# EXT_TWI_LVC.net
KiCad netlist of a schematic drawn in EAGLE
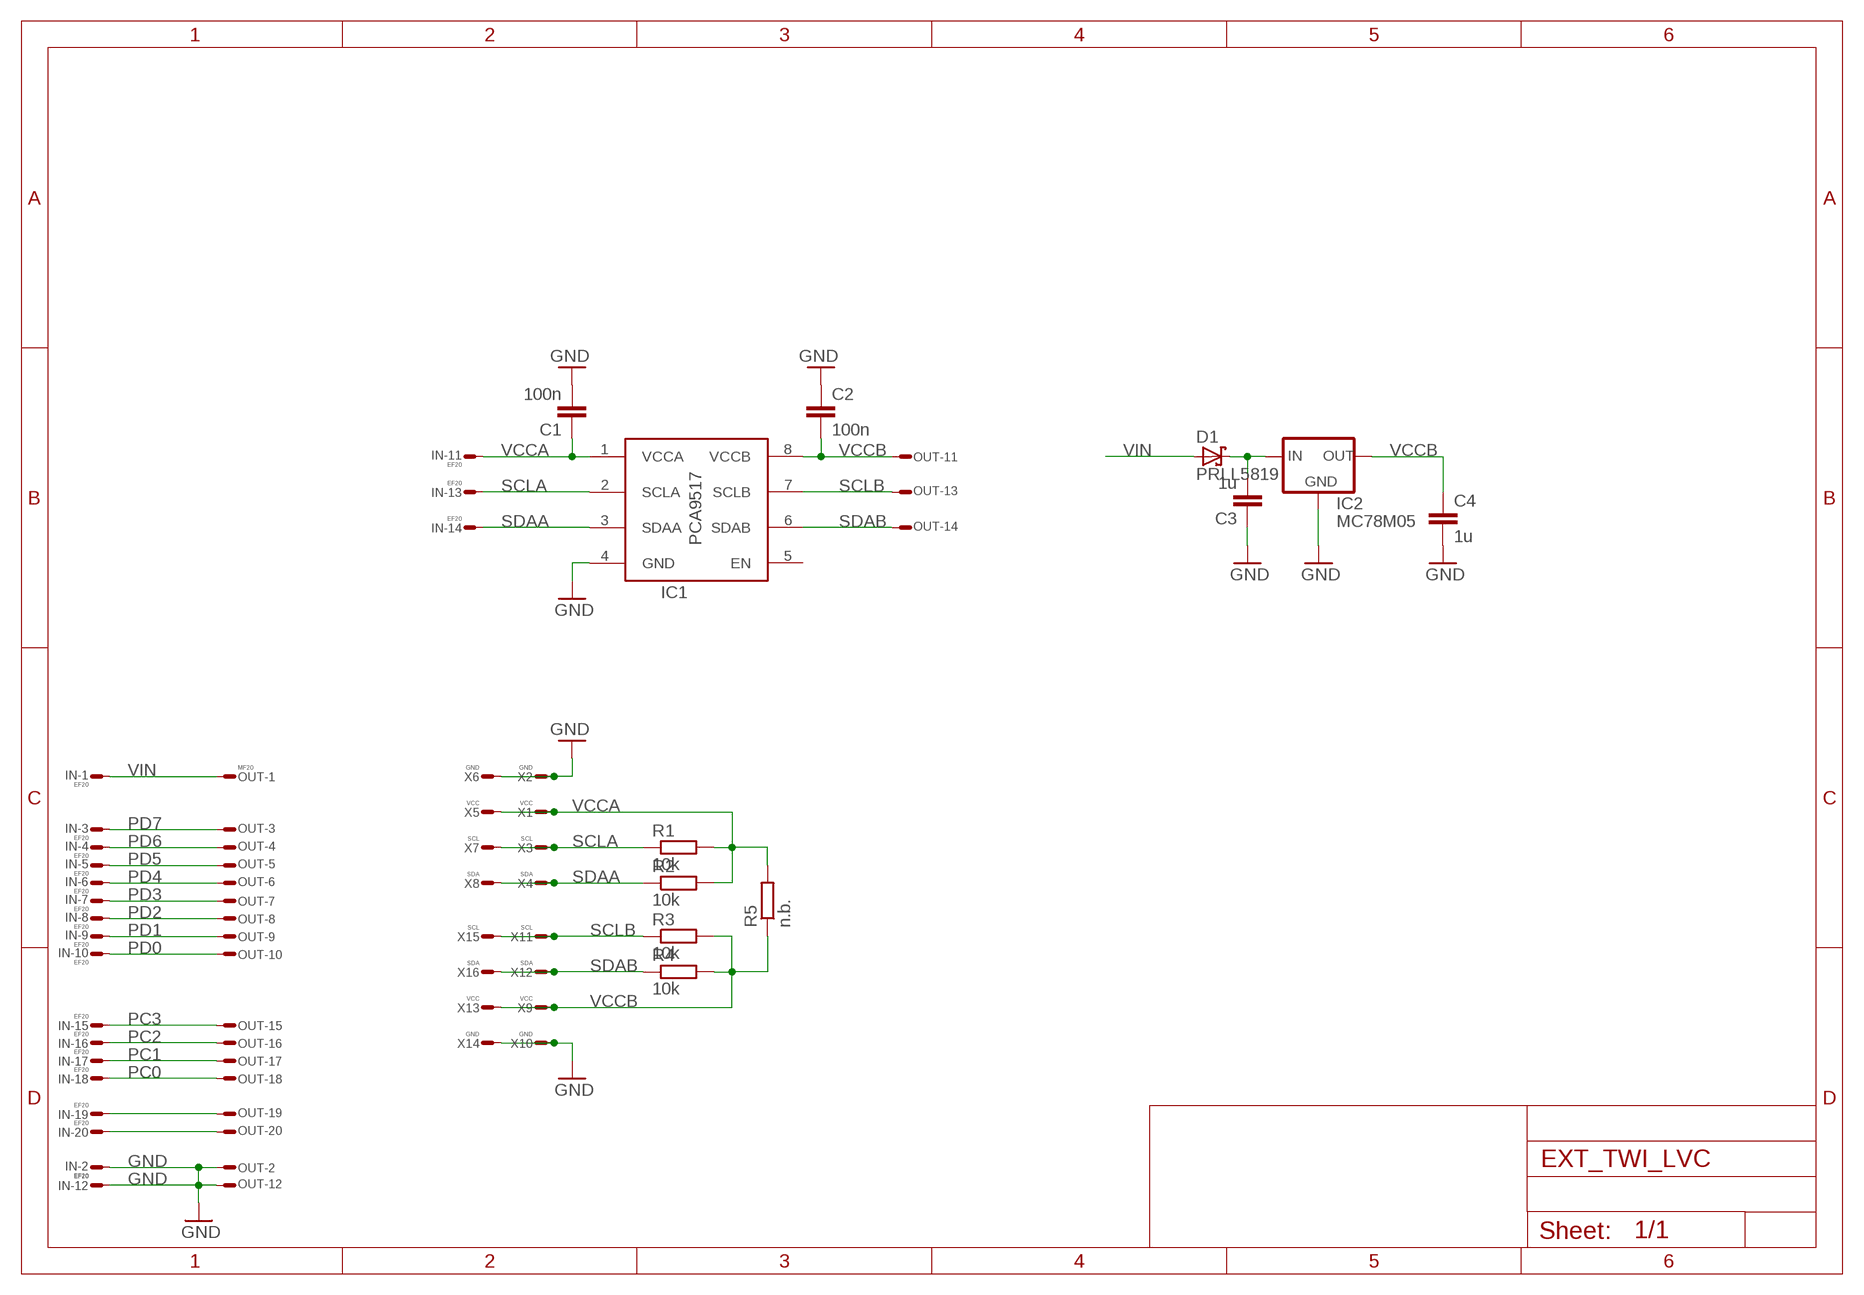
[diagram p0: schematic, sheet 1]

(export (version "E")
  (design (tool "Eeschema 10.0.6"))
  (components
    (comp (ref "C1")
      (value "100n")
      (footprint "eagle-import:0603")
      (libsource (lib "eagle-import") (part "C0603"))
    )
    (comp (ref "C2")
      (value "100n")
      (footprint "eagle-import:0603")
      (libsource (lib "eagle-import") (part "C0603"))
    )
    (comp (ref "C3")
      (value "1u")
      (footprint "eagle-import:1206")
      (libsource (lib "eagle-import") (part "C1206"))
    )
    (comp (ref "C4")
      (value "1u")
      (footprint "eagle-import:1206")
      (libsource (lib "eagle-import") (part "C1206"))
    )
    (comp (ref "D1")
      (value "PRLL5819")
      (footprint "eagle-import:SOD87")
      (libsource (lib "eagle-import") (part "D-SCHOTKY7"))
    )
    (comp (ref "IC1")
      (value "PCA9517")
      (footprint "eagle-import:SOIC8")
      (libsource (lib "eagle-import") (part "PCA9517D"))
    )
    (comp (ref "IC2")
      (value "MC78M05")
      (footprint "eagle-import:DPAK")
      (libsource (lib "eagle-import") (part "78XXD"))
    )
    (comp (ref "IN")
      (value "EF20")
      (footprint "eagle-import:FE10-2WSS")
      (libsource (lib "eagle-import") (part "FE20ELSS"))
    )
    (comp (ref "OUT")
      (value "MF20")
      (footprint "eagle-import:ML20LS")
      (libsource (lib "eagle-import") (part "ML20?ELS"))
    )
    (comp (ref "R1")
      (value "10k")
      (footprint "eagle-import:0603")
      (libsource (lib "eagle-import") (part "R0603"))
    )
    (comp (ref "R2")
      (value "10k")
      (footprint "eagle-import:0603")
      (libsource (lib "eagle-import") (part "R0603"))
    )
    (comp (ref "R3")
      (value "10k")
      (footprint "eagle-import:0603")
      (libsource (lib "eagle-import") (part "R0603"))
    )
    (comp (ref "R4")
      (value "10k")
      (footprint "eagle-import:0603")
      (libsource (lib "eagle-import") (part "R0603"))
    )
    (comp (ref "R5")
      (value "n.b.")
      (footprint "eagle-import:1206")
      (libsource (lib "eagle-import") (part "R1206"))
    )
    (comp (ref "X1")
      (value "VCC")
      (footprint "eagle-import:T1.6_0.9")
      (libsource (lib "eagle-import") (part "WIREPADT1.6/0.9"))
    )
    (comp (ref "X2")
      (value "GND")
      (footprint "eagle-import:T1.6_0.9")
      (libsource (lib "eagle-import") (part "WIREPADT1.6/0.9"))
    )
    (comp (ref "X3")
      (value "SCL")
      (footprint "eagle-import:T1.6_0.9")
      (libsource (lib "eagle-import") (part "WIREPADT1.6/0.9"))
    )
    (comp (ref "X4")
      (value "SDA")
      (footprint "eagle-import:T1.6_0.9")
      (libsource (lib "eagle-import") (part "WIREPADT1.6/0.9"))
    )
    (comp (ref "X5")
      (value "VCC")
      (footprint "eagle-import:T1.6_0.9")
      (libsource (lib "eagle-import") (part "WIREPADT1.6/0.9"))
    )
    (comp (ref "X6")
      (value "GND")
      (footprint "eagle-import:T1.6_0.9")
      (libsource (lib "eagle-import") (part "WIREPADT1.6/0.9"))
    )
    (comp (ref "X7")
      (value "SCL")
      (footprint "eagle-import:T1.6_0.9")
      (libsource (lib "eagle-import") (part "WIREPADT1.6/0.9"))
    )
    (comp (ref "X8")
      (value "SDA")
      (footprint "eagle-import:T1.6_0.9")
      (libsource (lib "eagle-import") (part "WIREPADT1.6/0.9"))
    )
    (comp (ref "X9")
      (value "VCC")
      (footprint "eagle-import:T1.6_0.9")
      (libsource (lib "eagle-import") (part "WIREPADT1.6/0.9"))
    )
    (comp (ref "X10")
      (value "GND")
      (footprint "eagle-import:T1.6_0.9")
      (libsource (lib "eagle-import") (part "WIREPADT1.6/0.9"))
    )
    (comp (ref "X11")
      (value "SCL")
      (footprint "eagle-import:T1.6_0.9")
      (libsource (lib "eagle-import") (part "WIREPADT1.6/0.9"))
    )
    (comp (ref "X12")
      (value "SDA")
      (footprint "eagle-import:T1.6_0.9")
      (libsource (lib "eagle-import") (part "WIREPADT1.6/0.9"))
    )
    (comp (ref "X13")
      (value "VCC")
      (footprint "eagle-import:T1.6_0.9")
      (libsource (lib "eagle-import") (part "WIREPADT1.6/0.9"))
    )
    (comp (ref "X14")
      (value "GND")
      (footprint "eagle-import:T1.6_0.9")
      (libsource (lib "eagle-import") (part "WIREPADT1.6/0.9"))
    )
    (comp (ref "X15")
      (value "SCL")
      (footprint "eagle-import:T1.6_0.9")
      (libsource (lib "eagle-import") (part "WIREPADT1.6/0.9"))
    )
    (comp (ref "X16")
      (value "SDA")
      (footprint "eagle-import:T1.6_0.9")
      (libsource (lib "eagle-import") (part "WIREPADT1.6/0.9"))
    )
  )
  (nets
    (net (code "1") (name "/PC0") (class "Default")
      (node (ref "IN") (pin "P$18") (pinfunction "S_P$18") (pintype "passive"))
      (node (ref "OUT") (pin "P$18") (pinfunction "S_P$18") (pintype "passive"))
    )
    (net (code "2") (name "/PC1") (class "Default")
      (node (ref "IN") (pin "P$17") (pinfunction "S_P$17") (pintype "passive"))
      (node (ref "OUT") (pin "P$17") (pinfunction "S_P$17") (pintype "passive"))
    )
    (net (code "3") (name "/PC2") (class "Default")
      (node (ref "IN") (pin "P$16") (pinfunction "S_P$16") (pintype "passive"))
      (node (ref "OUT") (pin "P$16") (pinfunction "S_P$16") (pintype "passive"))
    )
    (net (code "4") (name "/PC3") (class "Default")
      (node (ref "IN") (pin "P$15") (pinfunction "S_P$15") (pintype "passive"))
      (node (ref "OUT") (pin "P$15") (pinfunction "S_P$15") (pintype "passive"))
    )
    (net (code "5") (name "/PD0") (class "Default")
      (node (ref "IN") (pin "P$10") (pinfunction "S_P$10") (pintype "passive"))
      (node (ref "OUT") (pin "P$10") (pinfunction "S_P$10") (pintype "passive"))
    )
    (net (code "6") (name "/PD1") (class "Default")
      (node (ref "IN") (pin "P$9") (pinfunction "S_P$9") (pintype "passive"))
      (node (ref "OUT") (pin "P$9") (pinfunction "S_P$9") (pintype "passive"))
    )
    (net (code "7") (name "/PD2") (class "Default")
      (node (ref "IN") (pin "P$8") (pinfunction "S_P$8") (pintype "passive"))
      (node (ref "OUT") (pin "P$8") (pinfunction "S_P$8") (pintype "passive"))
    )
    (net (code "8") (name "/PD3") (class "Default")
      (node (ref "IN") (pin "P$7") (pinfunction "S_P$7") (pintype "passive"))
      (node (ref "OUT") (pin "P$7") (pinfunction "S_P$7") (pintype "passive"))
    )
    (net (code "9") (name "/PD4") (class "Default")
      (node (ref "IN") (pin "P$6") (pinfunction "S_P$6") (pintype "passive"))
      (node (ref "OUT") (pin "P$6") (pinfunction "S_P$6") (pintype "passive"))
    )
    (net (code "10") (name "/PD5") (class "Default")
      (node (ref "IN") (pin "P$5") (pinfunction "S_P$5") (pintype "passive"))
      (node (ref "OUT") (pin "P$5") (pinfunction "S_P$5") (pintype "passive"))
    )
    (net (code "11") (name "/PD6") (class "Default")
      (node (ref "IN") (pin "P$4") (pinfunction "S_P$4") (pintype "passive"))
      (node (ref "OUT") (pin "P$4") (pinfunction "S_P$4") (pintype "passive"))
    )
    (net (code "12") (name "/PD7") (class "Default")
      (node (ref "IN") (pin "P$3") (pinfunction "S_P$3") (pintype "passive"))
      (node (ref "OUT") (pin "P$3") (pinfunction "S_P$3") (pintype "passive"))
    )
    (net (code "13") (name "/SCLA") (class "Default")
      (node (ref "IC1") (pin "2") (pinfunction "SCLA_2") (pintype "bidirectional"))
      (node (ref "IN") (pin "P$13") (pinfunction "S_P$13") (pintype "passive"))
      (node (ref "R1") (pin "1") (pinfunction "1_1") (pintype "passive"))
      (node (ref "X3") (pin "1") (pinfunction "S_1") (pintype "passive"))
      (node (ref "X7") (pin "1") (pinfunction "S_1") (pintype "passive"))
    )
    (net (code "14") (name "/SCLB") (class "Default")
      (node (ref "IC1") (pin "7") (pinfunction "SCLB_7") (pintype "bidirectional"))
      (node (ref "OUT") (pin "P$13") (pinfunction "S_P$13") (pintype "passive"))
      (node (ref "R3") (pin "1") (pinfunction "1_1") (pintype "passive"))
      (node (ref "X11") (pin "1") (pinfunction "S_1") (pintype "passive"))
      (node (ref "X15") (pin "1") (pinfunction "S_1") (pintype "passive"))
    )
    (net (code "15") (name "/SDAA") (class "Default")
      (node (ref "IC1") (pin "3") (pinfunction "SDAA_3") (pintype "bidirectional"))
      (node (ref "IN") (pin "P$14") (pinfunction "S_P$14") (pintype "passive"))
      (node (ref "R2") (pin "1") (pinfunction "1_1") (pintype "passive"))
      (node (ref "X4") (pin "1") (pinfunction "S_1") (pintype "passive"))
      (node (ref "X8") (pin "1") (pinfunction "S_1") (pintype "passive"))
    )
    (net (code "16") (name "/SDAB") (class "Default")
      (node (ref "IC1") (pin "6") (pinfunction "SDAB_6") (pintype "bidirectional"))
      (node (ref "OUT") (pin "P$14") (pinfunction "S_P$14") (pintype "passive"))
      (node (ref "R4") (pin "1") (pinfunction "1_1") (pintype "passive"))
      (node (ref "X12") (pin "1") (pinfunction "S_1") (pintype "passive"))
      (node (ref "X16") (pin "1") (pinfunction "S_1") (pintype "passive"))
    )
    (net (code "17") (name "/VCCA") (class "Default")
      (node (ref "C1") (pin "1") (pinfunction "1_1") (pintype "passive"))
      (node (ref "IC1") (pin "1") (pinfunction "VCCA_1") (pintype "bidirectional"))
      (node (ref "IN") (pin "P$11") (pinfunction "S_P$11") (pintype "passive"))
      (node (ref "R1") (pin "2") (pinfunction "2_2") (pintype "passive"))
      (node (ref "R2") (pin "2") (pinfunction "2_2") (pintype "passive"))
      (node (ref "R5") (pin "2") (pinfunction "2_2") (pintype "passive"))
      (node (ref "X1") (pin "1") (pinfunction "S_1") (pintype "passive"))
      (node (ref "X5") (pin "1") (pinfunction "S_1") (pintype "passive"))
    )
    (net (code "18") (name "/VCCB") (class "Default")
      (node (ref "C2") (pin "2") (pinfunction "2_2") (pintype "passive"))
      (node (ref "C4") (pin "1") (pinfunction "1_1") (pintype "passive"))
      (node (ref "IC1") (pin "8") (pinfunction "VCCB_8") (pintype "bidirectional"))
      (node (ref "IC2") (pin "3") (pinfunction "OUT_3") (pintype "passive"))
      (node (ref "OUT") (pin "P$11") (pinfunction "S_P$11") (pintype "passive"))
      (node (ref "R3") (pin "2") (pinfunction "2_2") (pintype "passive"))
      (node (ref "R4") (pin "2") (pinfunction "2_2") (pintype "passive"))
      (node (ref "R5") (pin "1") (pinfunction "1_1") (pintype "passive"))
      (node (ref "X13") (pin "1") (pinfunction "S_1") (pintype "passive"))
      (node (ref "X9") (pin "1") (pinfunction "S_1") (pintype "passive"))
    )
    (net (code "19") (name "/VIN") (class "Default")
      (node (ref "D1") (pin "A") (pinfunction "A_A") (pintype "passive"))
      (node (ref "IN") (pin "P$1") (pinfunction "S_P$1") (pintype "passive"))
      (node (ref "OUT") (pin "P$1") (pinfunction "S_P$1") (pintype "passive"))
    )
    (net (code "20") (name "GND") (class "Default")
      (node (ref "C1") (pin "2") (pinfunction "2_2") (pintype "passive"))
      (node (ref "C2") (pin "1") (pinfunction "1_1") (pintype "passive"))
      (node (ref "C3") (pin "1") (pinfunction "1_1") (pintype "passive"))
      (node (ref "C4") (pin "2") (pinfunction "2_2") (pintype "passive"))
      (node (ref "IC1") (pin "4") (pinfunction "GND_4") (pintype "bidirectional"))
      (node (ref "IC2") (pin "4") (pinfunction "GND_4") (pintype "input"))
      (node (ref "IN") (pin "P$12") (pinfunction "S_P$12") (pintype "passive"))
      (node (ref "IN") (pin "P$2") (pinfunction "S_P$2") (pintype "passive"))
      (node (ref "OUT") (pin "P$12") (pinfunction "S_P$12") (pintype "passive"))
      (node (ref "OUT") (pin "P$2") (pinfunction "S_P$2") (pintype "passive"))
      (node (ref "X10") (pin "1") (pinfunction "S_1") (pintype "passive"))
      (node (ref "X14") (pin "1") (pinfunction "S_1") (pintype "passive"))
      (node (ref "X2") (pin "1") (pinfunction "S_1") (pintype "passive"))
      (node (ref "X6") (pin "1") (pinfunction "S_1") (pintype "passive"))
    )
    (net (code "21") (name "Net-(IC2-IN)") (class "Default")
      (node (ref "C3") (pin "2") (pinfunction "2_2") (pintype "passive"))
      (node (ref "D1") (pin "C") (pinfunction "C_C") (pintype "passive"))
      (node (ref "IC2") (pin "1") (pinfunction "IN_1") (pintype "input"))
    )
    (net (code "22") (name "Net-(INK-S)") (class "Default")
      (node (ref "IN") (pin "P$19") (pinfunction "S_P$19") (pintype "passive"))
      (node (ref "OUT") (pin "P$19") (pinfunction "S_P$19") (pintype "passive"))
    )
    (net (code "23") (name "Net-(INM-S)") (class "Default")
      (node (ref "IN") (pin "P$20") (pinfunction "S_P$20") (pintype "passive"))
      (node (ref "OUT") (pin "P$20") (pinfunction "S_P$20") (pintype "passive"))
    )
    (net (code "24") (name "unconnected-(IC1-EN-Pad5)") (class "Default")
      (node (ref "IC1") (pin "5") (pinfunction "EN_5") (pintype "bidirectional"))
    )
  )
)
